# power.net
KiCad netlist of a schematic drawn in Altium Designer
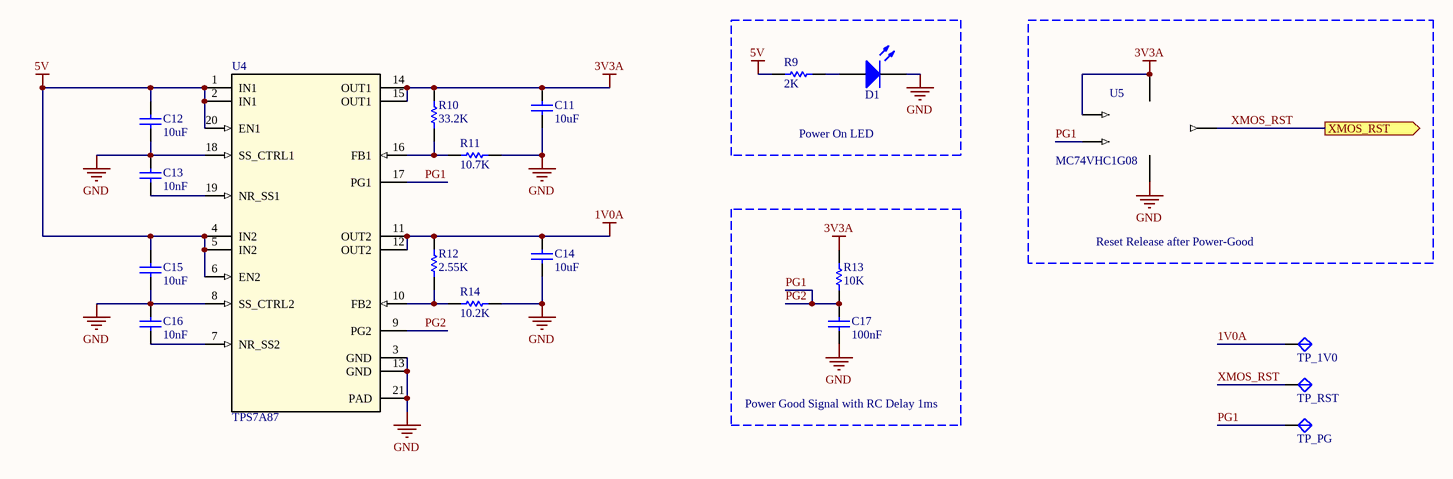
[diagram p0: power.SchDoc]

(export (version "E")
  (design (tool "Eeschema 10.0.6"))
  (components
    (comp (ref "C11")
      (value "10uF")
      (footprint "CAP_0603")
      (description "Multilayer Ceramic Capacitors")
      (fields (field (name "TOLERANCE") "10%") (field (name "Comment") "MLCC"))
      (libsource (lib "Capacitors") (part "MLCC"))
    )
    (comp (ref "C12")
      (value "10uF")
      (footprint "CAP_0603")
      (description "Multilayer Ceramic Capacitors")
      (fields (field (name "TOLERANCE") "10%") (field (name "Comment") "MLCC"))
      (libsource (lib "Capacitors") (part "MLCC"))
    )
    (comp (ref "C13")
      (value "10nF")
      (footprint "CAP_0603")
      (description "Multilayer Ceramic Capacitors")
      (fields (field (name "TOLERANCE") "10%") (field (name "Comment") "MLCC"))
      (libsource (lib "Capacitors") (part "MLCC"))
    )
    (comp (ref "C14")
      (value "10uF")
      (footprint "CAP_0603")
      (description "Multilayer Ceramic Capacitors")
      (fields (field (name "TOLERANCE") "10%") (field (name "Comment") "MLCC"))
      (libsource (lib "Capacitors") (part "MLCC"))
    )
    (comp (ref "C15")
      (value "10uF")
      (footprint "CAP_0603")
      (description "Multilayer Ceramic Capacitors")
      (fields (field (name "TOLERANCE") "10%") (field (name "Comment") "MLCC"))
      (libsource (lib "Capacitors") (part "MLCC"))
    )
    (comp (ref "C16")
      (value "10nF")
      (footprint "CAP_0603")
      (description "Multilayer Ceramic Capacitors")
      (fields (field (name "TOLERANCE") "10%") (field (name "Comment") "MLCC"))
      (libsource (lib "Capacitors") (part "MLCC"))
    )
    (comp (ref "C17")
      (value "100nF")
      (footprint "CAP_0603")
      (description "Multilayer Ceramic Capacitors")
      (fields (field (name "TOLERANCE") "10%") (field (name "Comment") "MLCC"))
      (libsource (lib "Capacitors") (part "MLCC"))
    )
    (comp (ref "D1")
      (value "LED")
      (footprint "0603_RED")
      (description "LED Emitters")
      (libsource (lib "Leds") (part "LED"))
    )
    (comp (ref "R9")
      (value "2K")
      (footprint "RC0603N")
      (description "Chip Resistors")
      (fields (field (name "Comment") "RES"))
      (libsource (lib "Resistors") (part "RES"))
    )
    (comp (ref "R10")
      (value "33.2K")
      (footprint "RC0603N")
      (description "Chip Resistors")
      (fields (field (name "Comment") "RES"))
      (libsource (lib "Resistors") (part "RES"))
    )
    (comp (ref "R11")
      (value "10.7K")
      (footprint "RC0603N")
      (description "Chip Resistors")
      (fields (field (name "Comment") "RES"))
      (libsource (lib "Resistors") (part "RES"))
    )
    (comp (ref "R12")
      (value "2.55K")
      (footprint "RC0603N")
      (description "Chip Resistors")
      (fields (field (name "Comment") "RES"))
      (libsource (lib "Resistors") (part "RES"))
    )
    (comp (ref "R13")
      (value "10K")
      (footprint "RC0603N")
      (description "Chip Resistors")
      (fields (field (name "Comment") "RES"))
      (libsource (lib "Resistors") (part "RES"))
    )
    (comp (ref "R14")
      (value "10.2K")
      (footprint "RC0603N")
      (description "Chip Resistors")
      (fields (field (name "Comment") "RES"))
      (libsource (lib "Resistors") (part "RES"))
    )
    (comp (ref "TP_1V0")
      (value "TestPoint")
      (footprint "TESTPOINT(1)")
      (description "Test Point")
      (libsource (lib "Connectors") (part "TestPoint"))
    )
    (comp (ref "TP_PG")
      (value "TestPoint")
      (footprint "TESTPOINT(1)")
      (description "Test Point")
      (libsource (lib "Connectors") (part "TestPoint"))
    )
    (comp (ref "TP_RST")
      (value "TestPoint")
      (footprint "TESTPOINT(1)")
      (description "Test Point")
      (libsource (lib "Connectors") (part "TestPoint"))
    )
    (comp (ref "U4")
      (value "TPS7A87")
      (footprint "RTJ20")
      (description "TPS7A87 Dual, 500-mA, Low-Noise (3.8 μVRMS), LDO Voltage Regulator")
      (fields
        (field (name "MANUFACTURER") "Texas Instruments")
        (field (name "MANUFACTURER_PART_NUMBER") "TPS7A8701RTJR")
        (field (name "COPYRIGHT") "Copyright (C) 2018 Accelerated Designs. All rights reserved")
      )
      (libsource (lib "TI") (part "TPS7A87"))
    )
    (comp (ref "U5")
      (value "MC74VHC1G08")
      (footprint "SC-88A")
      (description "Single 2-Input AND Gate")
      (libsource (lib "ON") (part "MC74VHC1G08"))
    )
  )
  (nets
    (net (code "1") (name "/PG1") (class "Default")
      (node (ref "C17") (pin "2") (pinfunction "2_2") (pintype "passive"))
      (node (ref "R13") (pin "2") (pinfunction "2_2") (pintype "passive"))
      (node (ref "TP_PG") (pin "1") (pinfunction "1_1") (pintype "passive"))
      (node (ref "U4") (pin "17") (pinfunction "PG1_17") (pintype "open_collector"))
      (node (ref "U4") (pin "9") (pinfunction "PG2_9") (pintype "open_collector"))
      (node (ref "U5") (pin "2") (pinfunction "A_2") (pintype "input"))
    )
    (net (code "2") (name "/XMOS_RST") (class "Default")
      (node (ref "TP_RST") (pin "1") (pinfunction "1_1") (pintype "passive"))
      (node (ref "U5") (pin "4") (pinfunction "Y_4") (pintype "output"))
    )
    (net (code "3") (name "1V0A") (class "Default")
      (node (ref "C14") (pin "2") (pinfunction "2_2") (pintype "passive"))
      (node (ref "R12") (pin "2") (pinfunction "2_2") (pintype "passive"))
      (node (ref "TP_1V0") (pin "1") (pinfunction "1_1") (pintype "passive"))
      (node (ref "U4") (pin "11") (pinfunction "OUT2_11") (pintype "power_in"))
      (node (ref "U4") (pin "12") (pinfunction "OUT2_12") (pintype "power_in"))
    )
    (net (code "4") (name "3V3A") (class "Default")
      (node (ref "C11") (pin "2") (pinfunction "2_2") (pintype "passive"))
      (node (ref "R10") (pin "2") (pinfunction "2_2") (pintype "passive"))
      (node (ref "R13") (pin "1") (pinfunction "1_1") (pintype "passive"))
      (node (ref "U4") (pin "14") (pinfunction "OUT1_14") (pintype "power_in"))
      (node (ref "U4") (pin "15") (pinfunction "OUT1_15") (pintype "power_in"))
      (node (ref "U5") (pin "1") (pinfunction "B_1") (pintype "input"))
      (node (ref "U5") (pin "5") (pinfunction "VCC_5") (pintype "passive"))
    )
    (net (code "5") (name "5V") (class "Default")
      (node (ref "C12") (pin "2") (pinfunction "2_2") (pintype "passive"))
      (node (ref "C15") (pin "2") (pinfunction "2_2") (pintype "passive"))
      (node (ref "R9") (pin "2") (pinfunction "2_2") (pintype "passive"))
      (node (ref "U4") (pin "1") (pinfunction "IN1_1") (pintype "power_in"))
      (node (ref "U4") (pin "2") (pinfunction "IN1_2") (pintype "power_in"))
      (node (ref "U4") (pin "20") (pinfunction "EN1_20") (pintype "input"))
      (node (ref "U4") (pin "4") (pinfunction "IN2_4") (pintype "power_in"))
      (node (ref "U4") (pin "5") (pinfunction "IN2_5") (pintype "power_in"))
      (node (ref "U4") (pin "6") (pinfunction "EN2_6") (pintype "input"))
    )
    (net (code "6") (name "GND") (class "Default")
      (node (ref "C11") (pin "1") (pinfunction "1_1") (pintype "passive"))
      (node (ref "C12") (pin "1") (pinfunction "1_1") (pintype "passive"))
      (node (ref "C13") (pin "2") (pinfunction "2_2") (pintype "passive"))
      (node (ref "C14") (pin "1") (pinfunction "1_1") (pintype "passive"))
      (node (ref "C15") (pin "1") (pinfunction "1_1") (pintype "passive"))
      (node (ref "C16") (pin "2") (pinfunction "2_2") (pintype "passive"))
      (node (ref "C17") (pin "1") (pinfunction "1_1") (pintype "passive"))
      (node (ref "D1") (pin "2") (pinfunction "K_2") (pintype "passive"))
      (node (ref "R11") (pin "1") (pinfunction "1_1") (pintype "passive"))
      (node (ref "R14") (pin "1") (pinfunction "1_1") (pintype "passive"))
      (node (ref "U4") (pin "13") (pinfunction "GND_13") (pintype "power_in"))
      (node (ref "U4") (pin "18") (pinfunction "SS_CTRL1_18") (pintype "input"))
      (node (ref "U4") (pin "21") (pinfunction "PAD_21") (pintype "power_in"))
      (node (ref "U4") (pin "3") (pinfunction "GND_3") (pintype "power_in"))
      (node (ref "U4") (pin "8") (pinfunction "SS_CTRL2_8") (pintype "input"))
      (node (ref "U5") (pin "3") (pinfunction "GND_3") (pintype "passive"))
    )
    (net (code "7") (name "Net-(D1-A)") (class "Default")
      (node (ref "D1") (pin "1") (pinfunction "A_1") (pintype "passive"))
      (node (ref "R9") (pin "1") (pinfunction "1_1") (pintype "passive"))
    )
    (net (code "8") (name "Net-(U4-FB1)") (class "Default")
      (node (ref "R10") (pin "1") (pinfunction "1_1") (pintype "passive"))
      (node (ref "R11") (pin "2") (pinfunction "2_2") (pintype "passive"))
      (node (ref "U4") (pin "16") (pinfunction "FB1_16") (pintype "input"))
    )
    (net (code "9") (name "Net-(U4-FB2)") (class "Default")
      (node (ref "R12") (pin "1") (pinfunction "1_1") (pintype "passive"))
      (node (ref "R14") (pin "2") (pinfunction "2_2") (pintype "passive"))
      (node (ref "U4") (pin "10") (pinfunction "FB2_10") (pintype "input"))
    )
    (net (code "10") (name "Net-(U4-NR_SS1)") (class "Default")
      (node (ref "C13") (pin "1") (pinfunction "1_1") (pintype "passive"))
      (node (ref "U4") (pin "19") (pinfunction "NR_SS1_19") (pintype "input"))
    )
    (net (code "11") (name "Net-(U4-NR_SS2)") (class "Default")
      (node (ref "C16") (pin "1") (pinfunction "1_1") (pintype "passive"))
      (node (ref "U4") (pin "7") (pinfunction "NR_SS2_7") (pintype "input"))
    )
  )
)
